# CAN.net
KiCad netlist of a schematic drawn in Altium Designer
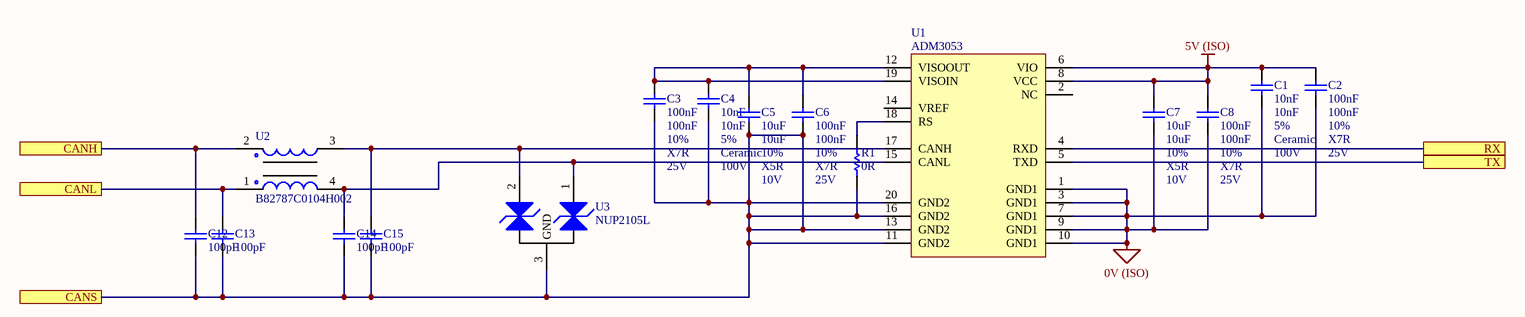
[diagram p0: CAN.SchDoc]

(export (version "E")
  (design (tool "Eeschema 10.0.6"))
  (components
    (comp (ref "C1")
      (value "10nF")
      (footprint "1206")
      (fields
        (field (name "ALTIUM_VALUE") "10nF")
        (field (name "TOLERANCE") "5%")
        (field (name "MATERIAL") "Ceramic")
        (field (name "RATED VOLTAGE") "100V")
        (field (name "PART NUMBER") "GCM3195C2A103JA16D")
        (field (name "MANUFACTURER") "muRata")
        (field (name "DIGIKEY PART NUMBER") "490-4978-2-ND")
      )
      (libsource (lib "ts_19-standard-library") (part "Capacitor"))
    )
    (comp (ref "C2")
      (value "100nF")
      (footprint "0805")
      (fields
        (field (name "ALTIUM_VALUE") "100nF")
        (field (name "TOLERANCE") "10%")
        (field (name "MATERIAL") "X7R")
        (field (name "RATED VOLTAGE") "25V")
        (field (name "PART NUMBER") "GCM21BR71E104KA37L")
        (field (name "MANUFACTURER") "muRata")
      )
      (libsource (lib "ts_19-standard-library") (part "Capacitor"))
    )
    (comp (ref "C3")
      (value "100nF")
      (footprint "0805")
      (fields
        (field (name "ALTIUM_VALUE") "100nF")
        (field (name "TOLERANCE") "10%")
        (field (name "MATERIAL") "X7R")
        (field (name "RATED VOLTAGE") "25V")
        (field (name "PART NUMBER") "GCM21BR71E104KA37L")
        (field (name "MANUFACTURER") "muRata")
      )
      (libsource (lib "ts_19-standard-library") (part "Capacitor"))
    )
    (comp (ref "C4")
      (value "10nF")
      (footprint "1206")
      (fields
        (field (name "ALTIUM_VALUE") "10nF")
        (field (name "TOLERANCE") "5%")
        (field (name "MATERIAL") "Ceramic")
        (field (name "RATED VOLTAGE") "100V")
        (field (name "PART NUMBER") "GCM3195C2A103JA16D")
        (field (name "MANUFACTURER") "muRata")
        (field (name "DIGIKEY PART NUMBER") "490-4978-2-ND")
      )
      (libsource (lib "ts_19-standard-library") (part "Capacitor"))
    )
    (comp (ref "C5")
      (value "10uF")
      (footprint "0805")
      (fields
        (field (name "ALTIUM_VALUE") "10uF")
        (field (name "TOLERANCE") "10%")
        (field (name "MATERIAL") "X5R")
        (field (name "RATED VOLTAGE") "10V")
        (field (name "PART NUMBER") "GCM21BR61A106KA37L")
        (field (name "MANUFACTURER") "muRata")
      )
      (libsource (lib "ts_19-standard-library") (part "Capacitor"))
    )
    (comp (ref "C6")
      (value "100nF")
      (footprint "0805")
      (fields
        (field (name "ALTIUM_VALUE") "100nF")
        (field (name "TOLERANCE") "10%")
        (field (name "MATERIAL") "X7R")
        (field (name "RATED VOLTAGE") "25V")
        (field (name "PART NUMBER") "GCM21BR71E104KA37L")
        (field (name "MANUFACTURER") "muRata")
      )
      (libsource (lib "ts_19-standard-library") (part "Capacitor"))
    )
    (comp (ref "C7")
      (value "10uF")
      (footprint "0805")
      (fields
        (field (name "ALTIUM_VALUE") "10uF")
        (field (name "TOLERANCE") "10%")
        (field (name "MATERIAL") "X5R")
        (field (name "RATED VOLTAGE") "10V")
        (field (name "PART NUMBER") "GCM21BR61A106KA37L")
        (field (name "MANUFACTURER") "muRata")
      )
      (libsource (lib "ts_19-standard-library") (part "Capacitor"))
    )
    (comp (ref "C8")
      (value "100nF")
      (footprint "0805")
      (fields
        (field (name "ALTIUM_VALUE") "100nF")
        (field (name "TOLERANCE") "10%")
        (field (name "MATERIAL") "X7R")
        (field (name "RATED VOLTAGE") "25V")
        (field (name "PART NUMBER") "GCM21BR71E104KA37L")
        (field (name "MANUFACTURER") "muRata")
      )
      (libsource (lib "ts_19-standard-library") (part "Capacitor"))
    )
    (comp (ref "C12")
      (value "100pF")
      (footprint "0805")
      (fields
        (field (name "PART NUMBER") "GCM21B5C1H101JA37L")
        (field (name "TOLERANCE") "5%")
        (field (name "MANUFACTURER") "muRata")
      )
      (libsource (lib "ts_19-standard-library") (part "Capacitor"))
    )
    (comp (ref "C13")
      (value "100pF")
      (footprint "0805")
      (fields
        (field (name "PART NUMBER") "GCM21B5C1H101JA37L")
        (field (name "TOLERANCE") "5%")
        (field (name "MANUFACTURER") "muRata")
      )
      (libsource (lib "ts_19-standard-library") (part "Capacitor"))
    )
    (comp (ref "C14")
      (value "100pF")
      (footprint "0805")
      (fields
        (field (name "PART NUMBER") "GCM21B5C1H101JA37L")
        (field (name "TOLERANCE") "5%")
        (field (name "MANUFACTURER") "muRata")
      )
      (libsource (lib "ts_19-standard-library") (part "Capacitor"))
    )
    (comp (ref "C15")
      (value "100pF")
      (footprint "0805")
      (fields
        (field (name "PART NUMBER") "GCM21B5C1H101JA37L")
        (field (name "TOLERANCE") "5%")
        (field (name "MANUFACTURER") "muRata")
      )
      (libsource (lib "ts_19-standard-library") (part "Capacitor"))
    )
    (comp (ref "R1")
      (value "0R")
      (footprint "0805")
      (fields
        (field (name "TOLERANCE") "0.01")
        (field (name "PART NUMBER") "RC0805FR070RL")
        (field (name "MANUFACTURER") "YAGEO")
      )
      (libsource (lib "ts_19-standard-library") (part "Resistor"))
    )
    (comp (ref "U1")
      (value "ADM3053")
      (footprint "AD SOIC-W 20")
      (description "Isolated CAN Transceiver")
      (fields
        (field (name "MANUFACTURER") "Analogue Devices")
        (field (name "DIGIKEY PART NUMBER") "ADM3053BRWZ-ND")
      )
      (libsource (lib "ts_19-standard-library") (part "ADM3053"))
    )
    (comp (ref "U2")
      (value "B82787C0104H002")
      (footprint "TDK 4-PC Pad")
      (description "Common mode choke intended for CANBUS 150mA 50V)")
      (fields
        (field (name "MANUFACTURER") "EPCOS (TDK)")
        (field (name "DIGIKEY PART NUMBER") "495-4598-2-ND")
      )
      (libsource (lib "ts_19-standard-library") (part "B82787C0104H002"))
    )
    (comp (ref "U3")
      (value "NUP2105L")
      (footprint "ON SOT-23")
      (description "Dual Line CAN Bus Protector")
      (fields
        (field (name "MANUFACTURER") "ON Semiconductor")
        (field (name "DIGIKEY PART NUMBER") "NUP2105LT1GOSCT-ND")
      )
      (libsource (lib "ts_19-standard-library") (part "NUP2105L"))
    )
  )
  (nets
    (net (code "1") (name "/CANH") (class "Default")
      (node (ref "C12") (pin "2") (pinfunction "2_2") (pintype "passive"))
      (node (ref "U2") (pin "2") (pinfunction "2_2") (pintype "passive"))
    )
    (net (code "2") (name "/CANL") (class "Default")
      (node (ref "C13") (pin "2") (pinfunction "2_2") (pintype "passive"))
      (node (ref "U2") (pin "1") (pinfunction "1_1") (pintype "passive"))
    )
    (net (code "3") (name "/CANS") (class "Default")
      (node (ref "C12") (pin "1") (pinfunction "1_1") (pintype "passive"))
      (node (ref "C13") (pin "1") (pinfunction "1_1") (pintype "passive"))
      (node (ref "C14") (pin "1") (pinfunction "1_1") (pintype "passive"))
      (node (ref "C15") (pin "1") (pinfunction "1_1") (pintype "passive"))
      (node (ref "C3") (pin "1") (pinfunction "1_1") (pintype "passive"))
      (node (ref "C4") (pin "1") (pinfunction "1_1") (pintype "passive"))
      (node (ref "C5") (pin "1") (pinfunction "1_1") (pintype "passive"))
      (node (ref "C6") (pin "1") (pinfunction "1_1") (pintype "passive"))
      (node (ref "R1") (pin "1") (pinfunction "1_1") (pintype "passive"))
      (node (ref "U1") (pin "11") (pinfunction "GND2_11") (pintype "passive"))
      (node (ref "U1") (pin "13") (pinfunction "GND2_13") (pintype "passive"))
      (node (ref "U1") (pin "16") (pinfunction "GND2_16") (pintype "passive"))
      (node (ref "U1") (pin "20") (pinfunction "GND2_20") (pintype "passive"))
      (node (ref "U3") (pin "3") (pinfunction "GND_3") (pintype "power_in"))
    )
    (net (code "4") (name "/RX") (class "Default")
      (node (ref "U1") (pin "4") (pinfunction "RXD_4") (pintype "passive"))
    )
    (net (code "5") (name "/TX") (class "Default")
      (node (ref "U1") (pin "5") (pinfunction "TXD_5") (pintype "passive"))
    )
    (net (code "6") (name "0V (ISO)") (class "Default")
      (node (ref "C1") (pin "1") (pinfunction "1_1") (pintype "passive"))
      (node (ref "C2") (pin "1") (pinfunction "1_1") (pintype "passive"))
      (node (ref "C7") (pin "1") (pinfunction "1_1") (pintype "passive"))
      (node (ref "C8") (pin "1") (pinfunction "1_1") (pintype "passive"))
      (node (ref "U1") (pin "1") (pinfunction "GND1_1") (pintype "passive"))
      (node (ref "U1") (pin "10") (pinfunction "GND1_10") (pintype "passive"))
      (node (ref "U1") (pin "3") (pinfunction "GND1_3") (pintype "passive"))
      (node (ref "U1") (pin "7") (pinfunction "GND1_7") (pintype "passive"))
      (node (ref "U1") (pin "9") (pinfunction "GND1_9") (pintype "passive"))
    )
    (net (code "7") (name "5V (ISO)") (class "Default")
      (node (ref "C1") (pin "2") (pinfunction "2_2") (pintype "passive"))
      (node (ref "C2") (pin "2") (pinfunction "2_2") (pintype "passive"))
      (node (ref "C7") (pin "2") (pinfunction "2_2") (pintype "passive"))
      (node (ref "C8") (pin "2") (pinfunction "2_2") (pintype "passive"))
      (node (ref "U1") (pin "6") (pinfunction "VIO_6") (pintype "passive"))
      (node (ref "U1") (pin "8") (pinfunction "VCC_8") (pintype "passive"))
    )
    (net (code "8") (name "Net-(U1-CANH)") (class "Default")
      (node (ref "C15") (pin "2") (pinfunction "2_2") (pintype "passive"))
      (node (ref "U1") (pin "17") (pinfunction "CANH_17") (pintype "passive"))
      (node (ref "U2") (pin "3") (pinfunction "3_3") (pintype "power_in"))
      (node (ref "U3") (pin "2") (pinfunction "CAN_L_2") (pintype "passive"))
    )
    (net (code "9") (name "Net-(U1-CANL)") (class "Default")
      (node (ref "C14") (pin "2") (pinfunction "2_2") (pintype "passive"))
      (node (ref "U1") (pin "15") (pinfunction "CANL_15") (pintype "passive"))
      (node (ref "U2") (pin "4") (pinfunction "4_4") (pintype "passive"))
      (node (ref "U3") (pin "1") (pinfunction "CAN_H_1") (pintype "passive"))
    )
    (net (code "10") (name "Net-(U1-RS)") (class "Default")
      (node (ref "R1") (pin "2") (pinfunction "2_2") (pintype "passive"))
      (node (ref "U1") (pin "18") (pinfunction "RS_18") (pintype "passive"))
    )
    (net (code "11") (name "Net-(U1-VISOIN)") (class "Default")
      (node (ref "C3") (pin "2") (pinfunction "2_2") (pintype "passive"))
      (node (ref "C4") (pin "2") (pinfunction "2_2") (pintype "passive"))
      (node (ref "C5") (pin "2") (pinfunction "2_2") (pintype "passive"))
      (node (ref "C6") (pin "2") (pinfunction "2_2") (pintype "passive"))
      (node (ref "U1") (pin "12") (pinfunction "VISOOUT_12") (pintype "passive"))
      (node (ref "U1") (pin "19") (pinfunction "VISOIN_19") (pintype "passive"))
    )
    (net (code "12") (name "unconnected-(U1-NC-Pad2)") (class "Default")
      (node (ref "U1") (pin "2") (pinfunction "NC_2") (pintype "passive"))
    )
    (net (code "13") (name "unconnected-(U1-VREF-Pad14)") (class "Default")
      (node (ref "U1") (pin "14") (pinfunction "VREF_14") (pintype "passive"))
    )
  )
)
